# LCD.net
KiCad netlist of a schematic drawn in Altium Designer
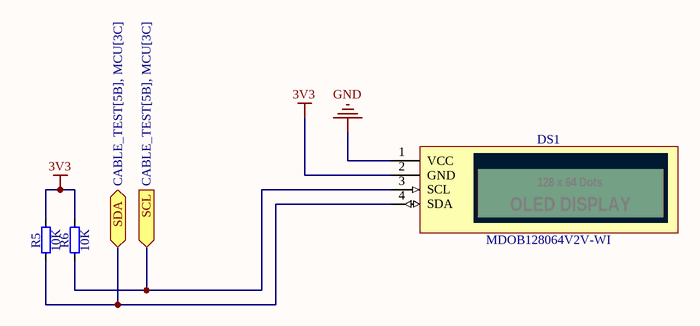
[diagram p0: LCD.SchDoc]

(export (version "E")
  (design (tool "Eeschema 10.0.6"))
  (components
    (comp (ref "DS1")
      (value "MDOB128064V2V-WI")
      (footprint "DS_MIDAS_MDOB128064V2V-WI")
      (description "LCD Display, Display Color White, I2C Bus Data Interface, 128 x 64 Dots Matrix")
      (fields
        (field (name "PART NUMBER") "DS_MIDAS_MDOB128064V2V-WI")
        (field (name "MANUFACTURER") "MIDAS DISPLAY")
        (field (name "AUTHOR") "CERN DEM BC")
      )
      (libsource (lib "ICs And Semiconductors") (part "DS_MIDAS_MDOB128064V2V-WI"))
    )
    (comp (ref "R5")
      (value "10K")
      (footprint "RESC2012X60N")
      (description "Resistor - 1%")
      (fields
        (field (name "PART NUMBER") "R0805_24K_1%_0.125W_100PPM")
        (field (name "POWER") "0.125W")
        (field (name "AUTHOR") "CERN DEM JLC")
      )
      (libsource (lib "Resistors") (part "Resistor - 1%"))
    )
    (comp (ref "R6")
      (value "10K")
      (footprint "RESC2012X60N")
      (description "Resistor - 1%")
      (fields
        (field (name "PART NUMBER") "R0805_24K_1%_0.125W_100PPM")
        (field (name "POWER") "0.125W")
        (field (name "AUTHOR") "CERN DEM JLC")
      )
      (libsource (lib "Resistors") (part "Resistor - 1%"))
    )
  )
  (nets
    (net (code "1") (name "/SCL") (class "Default")
      (node (ref "DS1") (pin "3") (pinfunction "SCL_3") (pintype "input"))
      (node (ref "R6") (pin "1") (pinfunction "1_1") (pintype "passive"))
    )
    (net (code "2") (name "/SDA") (class "Default")
      (node (ref "DS1") (pin "4") (pinfunction "SDA_4") (pintype "bidirectional"))
      (node (ref "R5") (pin "1") (pinfunction "1_1") (pintype "passive"))
    )
    (net (code "3") (name "3V3") (class "Default")
      (node (ref "DS1") (pin "2") (pinfunction "GND_2") (pintype "power_in"))
      (node (ref "R5") (pin "2") (pinfunction "2_2") (pintype "passive"))
      (node (ref "R6") (pin "2") (pinfunction "2_2") (pintype "passive"))
    )
    (net (code "4") (name "GND") (class "Default")
      (node (ref "DS1") (pin "1") (pinfunction "VCC_1") (pintype "power_in"))
    )
  )
)
